# smokeyamp.net
KiCad netlist of a schematic drawn in EAGLE
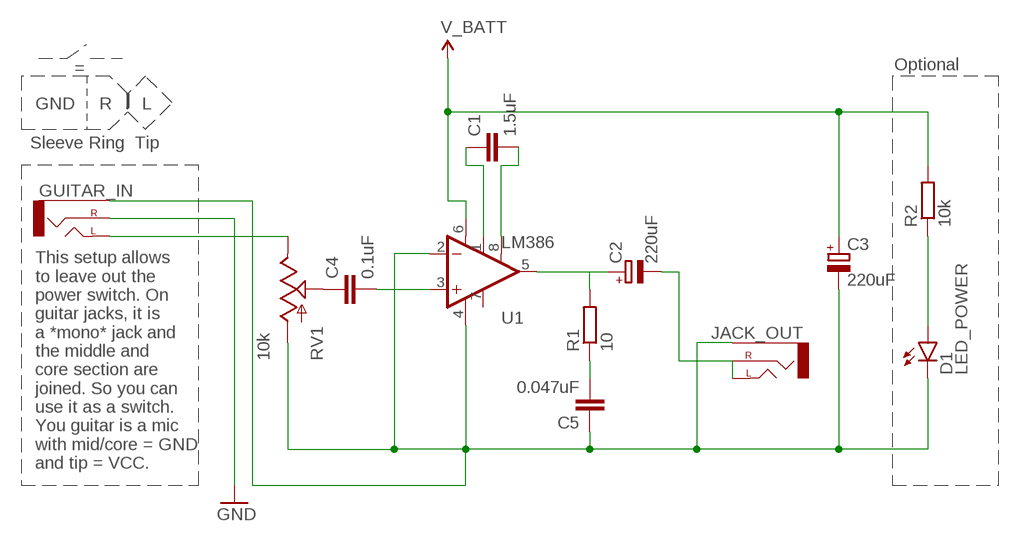
[diagram p0: schematic, sheet 1]

(export (version "E")
  (design (tool "Eeschema 10.0.6"))
  (components
    (comp (ref "C1")
      (value "1.5uF")
      (footprint "eagle-import:C025-024X044")
      (libsource (lib "eagle-import") (part "C-EU025-024X044"))
    )
    (comp (ref "C2")
      (value "220uF")
      (footprint "eagle-import:E2,5-5")
      (libsource (lib "eagle-import") (part "CPOL-EUE2.5-5"))
    )
    (comp (ref "C3")
      (value "220uF")
      (footprint "eagle-import:E2,5-5")
      (libsource (lib "eagle-import") (part "CPOL-EUE2.5-5"))
    )
    (comp (ref "C4")
      (value "0.1uF")
      (footprint "eagle-import:C025-024X044")
      (libsource (lib "eagle-import") (part "C-EU025-024X044"))
    )
    (comp (ref "C5")
      (value "0.047uF")
      (footprint "eagle-import:C025-024X044")
      (libsource (lib "eagle-import") (part "C-EU025-024X044"))
    )
    (comp (ref "D1")
      (value "LED_POWER")
      (footprint "eagle-import:FKIT-LED-1206")
      (libsource (lib "eagle-import") (part "LED-FKIT-1206"))
    )
    (comp (ref "GUITAR_IN")
      (value "AUDIO-JACK2.5MM")
      (footprint "eagle-import:STEREOJACK2.5MM_STEREOJACK2.5MM")
      (libsource (lib "eagle-import") (part "AUDIO-JACK2.5MM"))
    )
    (comp (ref "JACK_OUT")
      (value "AUDIO-JACK2.5MM")
      (footprint "eagle-import:STEREOJACK2.5MM_STEREOJACK2.5MM")
      (libsource (lib "eagle-import") (part "AUDIO-JACK2.5MM"))
    )
    (comp (ref "R1")
      (value "10")
      (footprint "eagle-import:0207_10")
      (libsource (lib "eagle-import") (part "R-EU_0207/10"))
    )
    (comp (ref "R2")
      (value "10k")
      (footprint "eagle-import:0207_10")
      (libsource (lib "eagle-import") (part "R-EU_0207/10"))
    )
    (comp (ref "RV1")
      (value "10k")
      (footprint "eagle-import:POT_ALPHA_RV16AF-20")
      (libsource (lib "eagle-import") (part "POT-RV16AF-20"))
    )
    (comp (ref "U1")
      (value "LM386")
      (footprint "eagle-import:DIP08")
      (libsource (lib "eagle-import") (part "LM386"))
    )
  )
  (nets
    (net (code "1") (name "GND") (class "Default")
      (node (ref "GUITAR_IN") (pin "TIP") (pinfunction "RIGHT_TIP") (pintype "bidirectional"))
    )
    (net (code "2") (name "Net-(C1-Pad1)") (class "Default")
      (node (ref "C1") (pin "1") (pinfunction "1_1") (pintype "passive"))
      (node (ref "U1") (pin "1") (pinfunction "GAIN_1") (pintype "bidirectional"))
    )
    (net (code "3") (name "Net-(C1-Pad2)") (class "Default")
      (node (ref "C1") (pin "2") (pinfunction "2_2") (pintype "passive"))
      (node (ref "U1") (pin "8") (pinfunction "GAIN_8") (pintype "bidirectional"))
    )
    (net (code "4") (name "Net-(C5-Pad2)") (class "Default")
      (node (ref "C5") (pin "2") (pinfunction "2_2") (pintype "passive"))
      (node (ref "R1") (pin "1") (pinfunction "1_1") (pintype "passive"))
    )
    (net (code "5") (name "Net-(D1-PadA)") (class "Default")
      (node (ref "D1") (pin "A") (pinfunction "A_A") (pintype "passive"))
      (node (ref "R2") (pin "1") (pinfunction "1_1") (pintype "passive"))
    )
    (net (code "6") (name "Net-(GUITAR_IN-LEFT)") (class "Default")
      (node (ref "GUITAR_IN") (pin "SHIELD") (pinfunction "LEFT_SHIELD") (pintype "bidirectional"))
      (node (ref "RV1") (pin "3") (pinfunction "E_3") (pintype "passive"))
    )
    (net (code "7") (name "Net-(GUITAR_IN-SLEEVE)") (class "Default")
      (node (ref "C3") (pin "-") (pinfunction "-_-") (pintype "passive"))
      (node (ref "C5") (pin "1") (pinfunction "1_1") (pintype "passive"))
      (node (ref "D1") (pin "C") (pinfunction "C_C") (pintype "passive"))
      (node (ref "GUITAR_IN") (pin "RING1") (pinfunction "SLEEVE_RING1") (pintype "bidirectional"))
      (node (ref "JACK_OUT") (pin "RING1") (pinfunction "SLEEVE_RING1") (pintype "bidirectional"))
      (node (ref "RV1") (pin "1") (pinfunction "A_1") (pintype "passive"))
      (node (ref "U1") (pin "2") (pinfunction "-IN_2") (pintype "input"))
      (node (ref "U1") (pin "4") (pinfunction "V-_4") (pintype "power_in"))
    )
    (net (code "8") (name "Net-(JACK_OUT-LEFT)") (class "Default")
      (node (ref "C2") (pin "-") (pinfunction "-_-") (pintype "passive"))
      (node (ref "JACK_OUT") (pin "SHIELD") (pinfunction "LEFT_SHIELD") (pintype "bidirectional"))
      (node (ref "JACK_OUT") (pin "TIP") (pinfunction "RIGHT_TIP") (pintype "bidirectional"))
    )
    (net (code "9") (name "Net-(RV1-S)") (class "Default")
      (node (ref "C4") (pin "1") (pinfunction "1_1") (pintype "passive"))
      (node (ref "RV1") (pin "2") (pinfunction "S_2") (pintype "passive"))
    )
    (net (code "10") (name "Net-(U1-+IN)") (class "Default")
      (node (ref "C4") (pin "2") (pinfunction "2_2") (pintype "passive"))
      (node (ref "U1") (pin "3") (pinfunction "+IN_3") (pintype "input"))
    )
    (net (code "11") (name "Net-(U1-OUT)") (class "Default")
      (node (ref "C2") (pin "+") (pinfunction "+_+") (pintype "passive"))
      (node (ref "R1") (pin "2") (pinfunction "2_2") (pintype "passive"))
      (node (ref "U1") (pin "5") (pinfunction "OUT_5") (pintype "output"))
    )
    (net (code "12") (name "V_BATT") (class "Default")
      (node (ref "C3") (pin "+") (pinfunction "+_+") (pintype "passive"))
      (node (ref "R2") (pin "2") (pinfunction "2_2") (pintype "passive"))
      (node (ref "U1") (pin "6") (pinfunction "V+_6") (pintype "power_in"))
    )
    (net (code "13") (name "unconnected-(U1-BP-Pad7)") (class "Default")
      (node (ref "U1") (pin "7") (pinfunction "BP_7") (pintype "bidirectional"))
    )
  )
)
